# Front.net
KiCad netlist of a schematic drawn in EAGLE
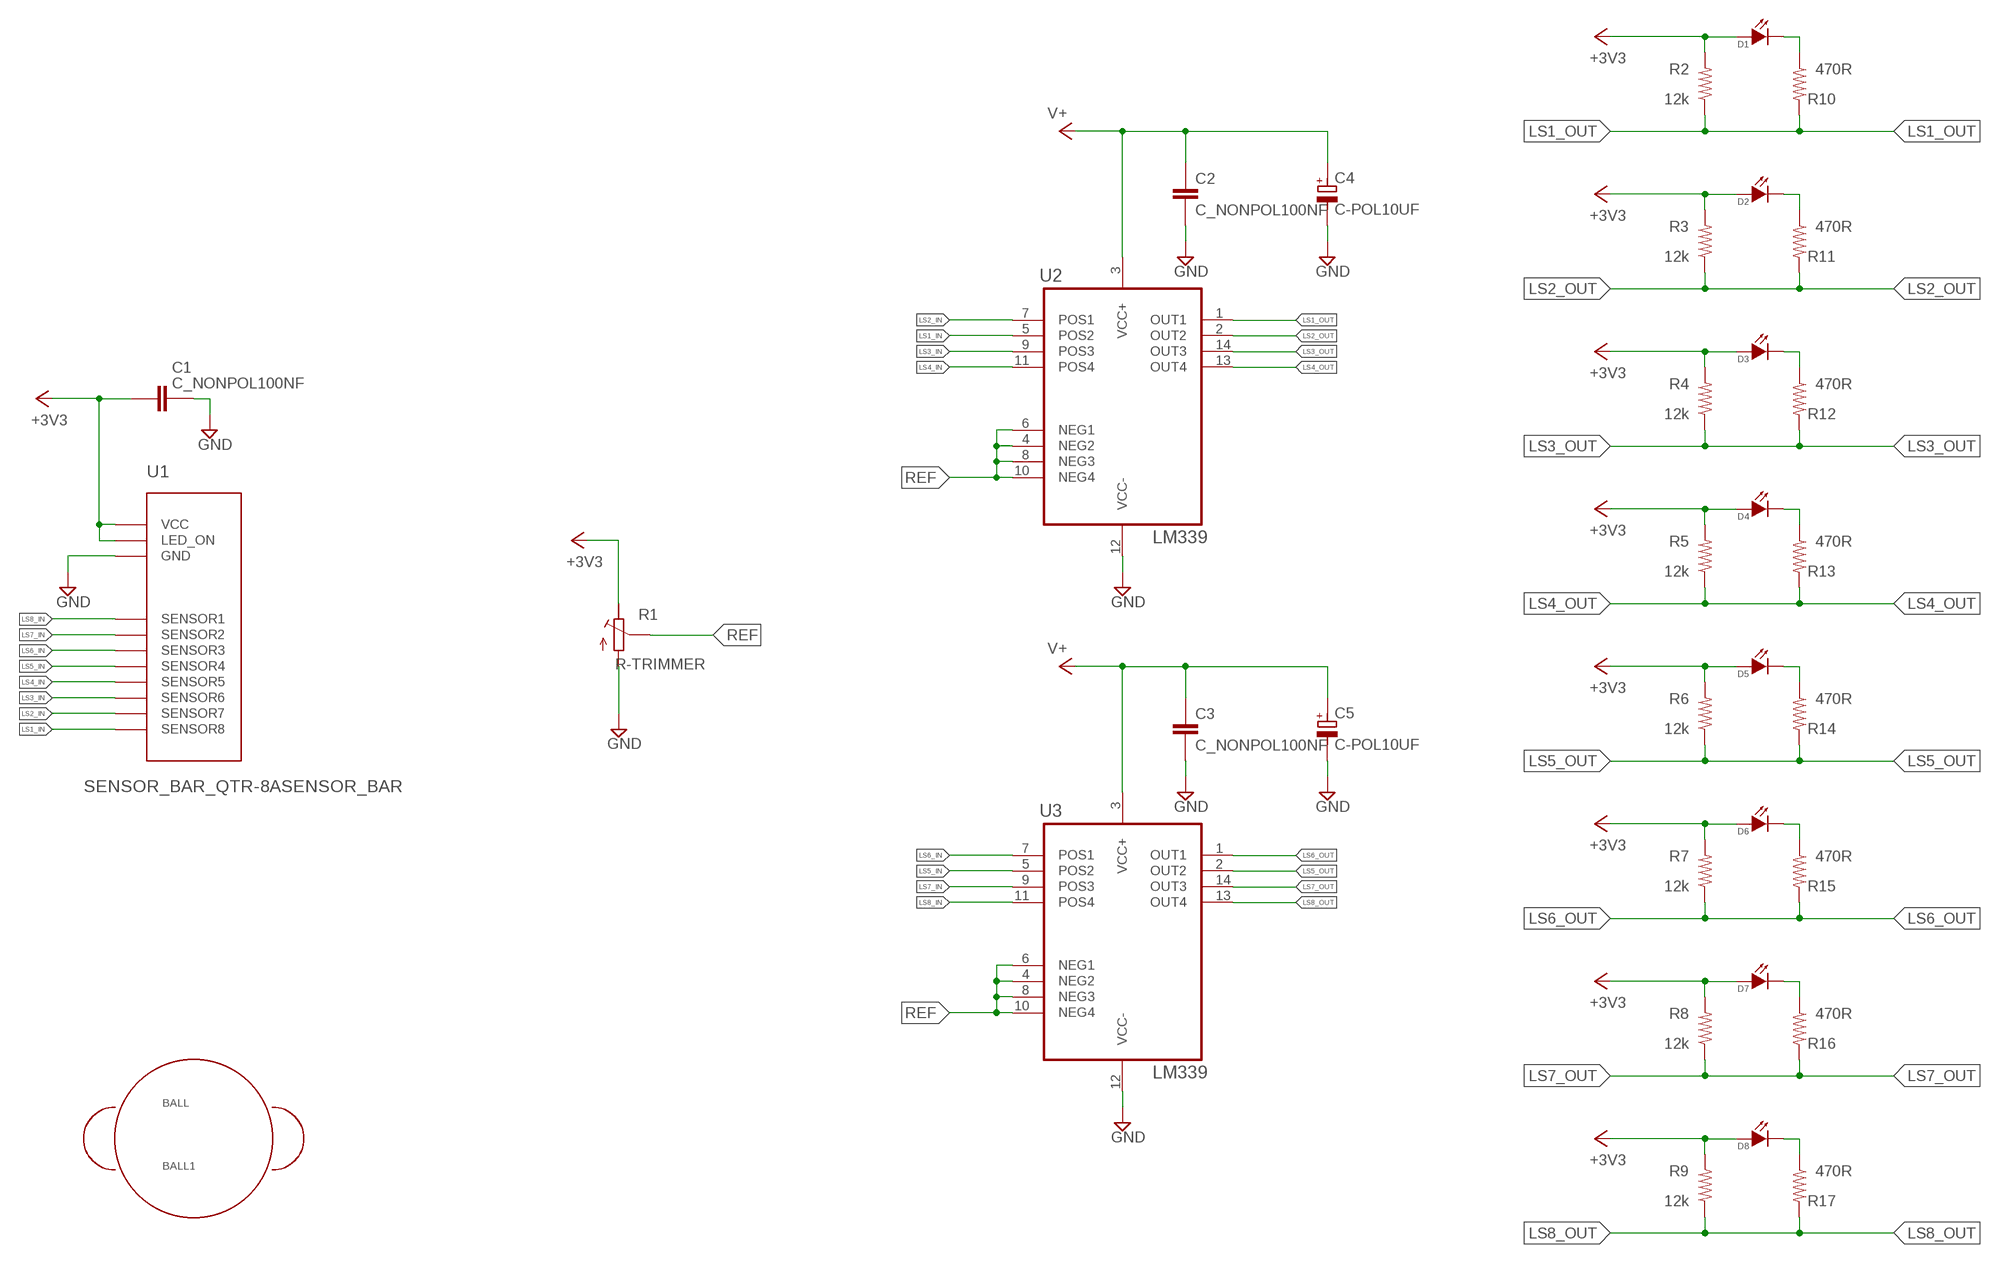
[diagram p0: schematic, sheet 1, part 1 of 2]
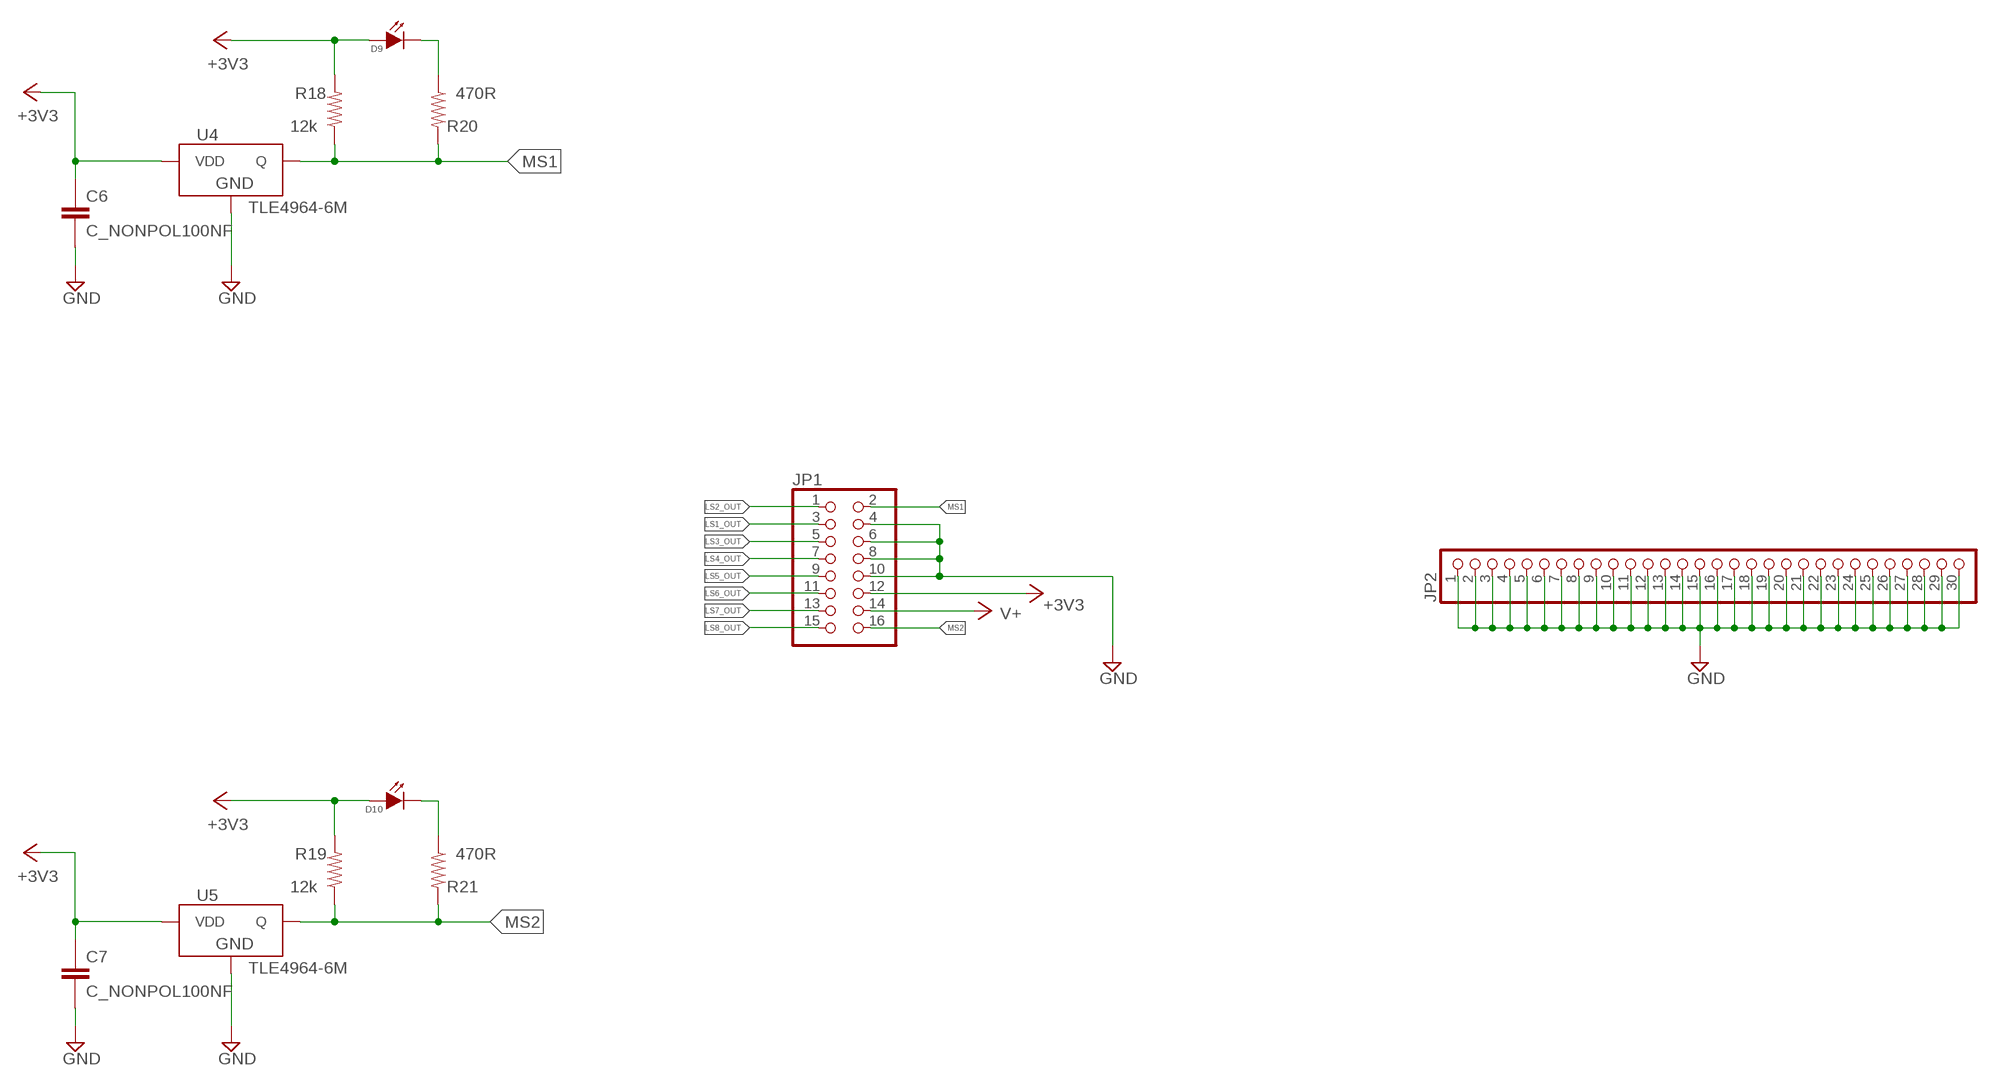
[diagram p1: schematic, sheet 1, part 2 of 2]

(export (version "E")
  (design (tool "Eeschema 10.0.6"))
  (components
    (comp (ref "BALL1")
      (value "BALL")
      (footprint "eagle-import:BALL")
      (libsource (lib "eagle-import") (part "BALL"))
    )
    (comp (ref "C1")
      (value "C_NONPOL100NF")
      (footprint "eagle-import:C1206")
      (libsource (lib "eagle-import") (part "C_NONPOL100NF"))
    )
    (comp (ref "C2")
      (value "C_NONPOL100NF")
      (footprint "eagle-import:C1206")
      (libsource (lib "eagle-import") (part "Line_Follower_LIBV3.1_C_NONPOL100NF"))
    )
    (comp (ref "C3")
      (value "C_NONPOL100NF")
      (footprint "eagle-import:C1206")
      (libsource (lib "eagle-import") (part "Line_Follower_LIBV3.1_C_NONPOL100NF"))
    )
    (comp (ref "C4")
      (value "C-POL10UF")
      (footprint "eagle-import:PANASONIC_B")
      (libsource (lib "eagle-import") (part "C-POL10UF"))
    )
    (comp (ref "C5")
      (value "C-POL10UF")
      (footprint "eagle-import:PANASONIC_B")
      (libsource (lib "eagle-import") (part "C-POL10UF"))
    )
    (comp (ref "C6")
      (value "C_NONPOL100NF")
      (footprint "eagle-import:C1206")
      (libsource (lib "eagle-import") (part "C_NONPOL100NF"))
    )
    (comp (ref "C7")
      (value "C_NONPOL100NF")
      (footprint "eagle-import:C1206")
      (libsource (lib "eagle-import") (part "C_NONPOL100NF"))
    )
    (comp (ref "D1")
      (value "LED")
      (footprint "eagle-import:CHIPLED_1206")
      (libsource (lib "eagle-import") (part "LED"))
    )
    (comp (ref "D2")
      (value "LED")
      (footprint "eagle-import:CHIPLED_1206")
      (libsource (lib "eagle-import") (part "LED"))
    )
    (comp (ref "D3")
      (value "LED")
      (footprint "eagle-import:CHIPLED_1206")
      (libsource (lib "eagle-import") (part "LED"))
    )
    (comp (ref "D4")
      (value "LED")
      (footprint "eagle-import:CHIPLED_1206")
      (libsource (lib "eagle-import") (part "LED"))
    )
    (comp (ref "D5")
      (value "LED")
      (footprint "eagle-import:CHIPLED_1206")
      (libsource (lib "eagle-import") (part "LED"))
    )
    (comp (ref "D6")
      (value "LED")
      (footprint "eagle-import:CHIPLED_1206")
      (libsource (lib "eagle-import") (part "LED"))
    )
    (comp (ref "D7")
      (value "LED")
      (footprint "eagle-import:CHIPLED_1206")
      (libsource (lib "eagle-import") (part "LED"))
    )
    (comp (ref "D8")
      (value "LED")
      (footprint "eagle-import:CHIPLED_1206")
      (libsource (lib "eagle-import") (part "LED"))
    )
    (comp (ref "D9")
      (value "LED")
      (footprint "eagle-import:CHIPLED_1206")
      (libsource (lib "eagle-import") (part "LED"))
    )
    (comp (ref "D10")
      (value "LED")
      (footprint "eagle-import:CHIPLED_1206")
      (libsource (lib "eagle-import") (part "LED"))
    )
    (comp (ref "JP1")
      (value "PINHD-2X8")
      (footprint "eagle-import:2X08")
      (libsource (lib "eagle-import") (part "PINHD-2X8"))
    )
    (comp (ref "JP2")
      (value "PINHD-1X30")
      (footprint "eagle-import:1X30")
      (libsource (lib "eagle-import") (part "PINHD-1X30"))
    )
    (comp (ref "R1")
      (value "R-TRIMMER")
      (footprint "eagle-import:TRIMMER")
      (libsource (lib "eagle-import") (part "R-TRIMMER"))
    )
    (comp (ref "R2")
      (value "12k")
      (footprint "eagle-import:R1206")
      (libsource (lib "eagle-import") (part "R1206"))
    )
    (comp (ref "R3")
      (value "12k")
      (footprint "eagle-import:R1206")
      (libsource (lib "eagle-import") (part "R1206"))
    )
    (comp (ref "R4")
      (value "12k")
      (footprint "eagle-import:R1206")
      (libsource (lib "eagle-import") (part "R1206"))
    )
    (comp (ref "R5")
      (value "12k")
      (footprint "eagle-import:R1206")
      (libsource (lib "eagle-import") (part "R1206"))
    )
    (comp (ref "R6")
      (value "12k")
      (footprint "eagle-import:R1206")
      (libsource (lib "eagle-import") (part "R1206"))
    )
    (comp (ref "R7")
      (value "12k")
      (footprint "eagle-import:R1206")
      (libsource (lib "eagle-import") (part "R1206"))
    )
    (comp (ref "R8")
      (value "12k")
      (footprint "eagle-import:R1206")
      (libsource (lib "eagle-import") (part "R1206"))
    )
    (comp (ref "R9")
      (value "12k")
      (footprint "eagle-import:R1206")
      (libsource (lib "eagle-import") (part "R1206"))
    )
    (comp (ref "R10")
      (value "470R")
      (footprint "eagle-import:R1206")
      (libsource (lib "eagle-import") (part "R1206"))
    )
    (comp (ref "R11")
      (value "470R")
      (footprint "eagle-import:R1206")
      (libsource (lib "eagle-import") (part "R1206"))
    )
    (comp (ref "R12")
      (value "470R")
      (footprint "eagle-import:R1206")
      (libsource (lib "eagle-import") (part "R1206"))
    )
    (comp (ref "R13")
      (value "470R")
      (footprint "eagle-import:R1206")
      (libsource (lib "eagle-import") (part "R1206"))
    )
    (comp (ref "R14")
      (value "470R")
      (footprint "eagle-import:R1206")
      (libsource (lib "eagle-import") (part "R1206"))
    )
    (comp (ref "R15")
      (value "470R")
      (footprint "eagle-import:R1206")
      (libsource (lib "eagle-import") (part "R1206"))
    )
    (comp (ref "R16")
      (value "470R")
      (footprint "eagle-import:R1206")
      (libsource (lib "eagle-import") (part "R1206"))
    )
    (comp (ref "R17")
      (value "470R")
      (footprint "eagle-import:R1206")
      (libsource (lib "eagle-import") (part "R1206"))
    )
    (comp (ref "R18")
      (value "12k")
      (footprint "eagle-import:R1206")
      (libsource (lib "eagle-import") (part "R1206"))
    )
    (comp (ref "R19")
      (value "12k")
      (footprint "eagle-import:R1206")
      (libsource (lib "eagle-import") (part "R1206"))
    )
    (comp (ref "R20")
      (value "470R")
      (footprint "eagle-import:R1206")
      (libsource (lib "eagle-import") (part "R1206"))
    )
    (comp (ref "R21")
      (value "470R")
      (footprint "eagle-import:R1206")
      (libsource (lib "eagle-import") (part "R1206"))
    )
    (comp (ref "U1")
      (value "SENSOR_BAR_QTR-8ASENSOR_BAR")
      (footprint "eagle-import:QTR-8A")
      (libsource (lib "eagle-import") (part "SENSOR_BAR_QTR-8ASENSOR_BAR"))
    )
    (comp (ref "U2")
      (value "LM339")
      (footprint "eagle-import:SO14")
      (libsource (lib "eagle-import") (part "LM339"))
    )
    (comp (ref "U3")
      (value "LM339")
      (footprint "eagle-import:SO14")
      (libsource (lib "eagle-import") (part "LM339"))
    )
    (comp (ref "U4")
      (value "TLE4964-6M")
      (footprint "eagle-import:SOT23-3")
      (libsource (lib "eagle-import") (part "TLE4964-6M"))
    )
    (comp (ref "U5")
      (value "TLE4964-6M")
      (footprint "eagle-import:SOT23-3")
      (libsource (lib "eagle-import") (part "TLE4964-6M"))
    )
  )
  (nets
    (net (code "1") (name "+3V3") (class "Default")
      (node (ref "C1") (pin "2") (pinfunction "2_2") (pintype "passive"))
      (node (ref "C6") (pin "1") (pinfunction "1_1") (pintype "passive"))
      (node (ref "C7") (pin "1") (pinfunction "1_1") (pintype "passive"))
      (node (ref "D1") (pin "A") (pinfunction "A_A") (pintype "bidirectional"))
      (node (ref "D10") (pin "A") (pinfunction "A_A") (pintype "bidirectional"))
      (node (ref "D2") (pin "A") (pinfunction "A_A") (pintype "bidirectional"))
      (node (ref "D3") (pin "A") (pinfunction "A_A") (pintype "bidirectional"))
      (node (ref "D4") (pin "A") (pinfunction "A_A") (pintype "bidirectional"))
      (node (ref "D5") (pin "A") (pinfunction "A_A") (pintype "bidirectional"))
      (node (ref "D6") (pin "A") (pinfunction "A_A") (pintype "bidirectional"))
      (node (ref "D7") (pin "A") (pinfunction "A_A") (pintype "bidirectional"))
      (node (ref "D8") (pin "A") (pinfunction "A_A") (pintype "bidirectional"))
      (node (ref "D9") (pin "A") (pinfunction "A_A") (pintype "bidirectional"))
      (node (ref "JP1") (pin "12") (pinfunction "12_12") (pintype "passive"))
      (node (ref "R1") (pin "2") (pinfunction "E_2") (pintype "passive"))
      (node (ref "R18") (pin "2") (pinfunction "P$2_2") (pintype "passive"))
      (node (ref "R19") (pin "2") (pinfunction "P$2_2") (pintype "passive"))
      (node (ref "R2") (pin "2") (pinfunction "P$2_2") (pintype "passive"))
      (node (ref "R3") (pin "2") (pinfunction "P$2_2") (pintype "passive"))
      (node (ref "R4") (pin "2") (pinfunction "P$2_2") (pintype "passive"))
      (node (ref "R5") (pin "2") (pinfunction "P$2_2") (pintype "passive"))
      (node (ref "R6") (pin "2") (pinfunction "P$2_2") (pintype "passive"))
      (node (ref "R7") (pin "2") (pinfunction "P$2_2") (pintype "passive"))
      (node (ref "R8") (pin "2") (pinfunction "P$2_2") (pintype "passive"))
      (node (ref "R9") (pin "2") (pinfunction "P$2_2") (pintype "passive"))
      (node (ref "U1") (pin "P$2") (pinfunction "LED_ON_P$2") (pintype "input"))
      (node (ref "U1") (pin "P$4") (pinfunction "VCC_P$4") (pintype "power_in"))
      (node (ref "U4") (pin "1") (pinfunction "VDD_1") (pintype "bidirectional"))
      (node (ref "U5") (pin "1") (pinfunction "VDD_1") (pintype "bidirectional"))
    )
    (net (code "2") (name "GND") (class "Default")
      (node (ref "C1") (pin "1") (pinfunction "1_1") (pintype "passive"))
      (node (ref "C2") (pin "2") (pinfunction "2_2") (pintype "passive"))
      (node (ref "C3") (pin "2") (pinfunction "2_2") (pintype "passive"))
      (node (ref "C4") (pin "-") (pinfunction "-_-") (pintype "passive"))
      (node (ref "C5") (pin "-") (pinfunction "-_-") (pintype "passive"))
      (node (ref "C6") (pin "2") (pinfunction "2_2") (pintype "passive"))
      (node (ref "C7") (pin "2") (pinfunction "2_2") (pintype "passive"))
      (node (ref "JP1") (pin "10") (pinfunction "10_10") (pintype "passive"))
      (node (ref "JP1") (pin "4") (pinfunction "4_4") (pintype "passive"))
      (node (ref "JP1") (pin "6") (pinfunction "6_6") (pintype "passive"))
      (node (ref "JP1") (pin "8") (pinfunction "8_8") (pintype "passive"))
      (node (ref "JP2") (pin "1") (pinfunction "1_1") (pintype "passive"))
      (node (ref "JP2") (pin "10") (pinfunction "10_10") (pintype "passive"))
      (node (ref "JP2") (pin "11") (pinfunction "11_11") (pintype "passive"))
      (node (ref "JP2") (pin "12") (pinfunction "12_12") (pintype "passive"))
      (node (ref "JP2") (pin "13") (pinfunction "13_13") (pintype "passive"))
      (node (ref "JP2") (pin "14") (pinfunction "14_14") (pintype "passive"))
      (node (ref "JP2") (pin "15") (pinfunction "15_15") (pintype "passive"))
      (node (ref "JP2") (pin "16") (pinfunction "16_16") (pintype "passive"))
      (node (ref "JP2") (pin "17") (pinfunction "17_17") (pintype "passive"))
      (node (ref "JP2") (pin "18") (pinfunction "18_18") (pintype "passive"))
      (node (ref "JP2") (pin "19") (pinfunction "19_19") (pintype "passive"))
      (node (ref "JP2") (pin "2") (pinfunction "2_2") (pintype "passive"))
      (node (ref "JP2") (pin "20") (pinfunction "20_20") (pintype "passive"))
      (node (ref "JP2") (pin "21") (pinfunction "21_21") (pintype "passive"))
      (node (ref "JP2") (pin "22") (pinfunction "22_22") (pintype "passive"))
      (node (ref "JP2") (pin "23") (pinfunction "23_23") (pintype "passive"))
      (node (ref "JP2") (pin "24") (pinfunction "24_24") (pintype "passive"))
      (node (ref "JP2") (pin "25") (pinfunction "25_25") (pintype "passive"))
      (node (ref "JP2") (pin "26") (pinfunction "26_26") (pintype "passive"))
      (node (ref "JP2") (pin "27") (pinfunction "27_27") (pintype "passive"))
      (node (ref "JP2") (pin "28") (pinfunction "28_28") (pintype "passive"))
      (node (ref "JP2") (pin "29") (pinfunction "29_29") (pintype "passive"))
      (node (ref "JP2") (pin "3") (pinfunction "3_3") (pintype "passive"))
      (node (ref "JP2") (pin "30") (pinfunction "30_30") (pintype "passive"))
      (node (ref "JP2") (pin "4") (pinfunction "4_4") (pintype "passive"))
      (node (ref "JP2") (pin "5") (pinfunction "5_5") (pintype "passive"))
      (node (ref "JP2") (pin "6") (pinfunction "6_6") (pintype "passive"))
      (node (ref "JP2") (pin "7") (pinfunction "7_7") (pintype "passive"))
      (node (ref "JP2") (pin "8") (pinfunction "8_8") (pintype "passive"))
      (node (ref "JP2") (pin "9") (pinfunction "9_9") (pintype "passive"))
      (node (ref "R1") (pin "1") (pinfunction "A_1") (pintype "passive"))
      (node (ref "U1") (pin "P$10") (pinfunction "GND_P$10") (pintype "power_in"))
      (node (ref "U1") (pin "P$12") (pinfunction "GND_P$12") (pintype "power_in"))
      (node (ref "U1") (pin "P$14") (pinfunction "GND_P$14") (pintype "power_in"))
      (node (ref "U1") (pin "P$16") (pinfunction "GND_P$16") (pintype "power_in"))
      (node (ref "U1") (pin "P$6") (pinfunction "GND_P$6") (pintype "power_in"))
      (node (ref "U1") (pin "P$8") (pinfunction "GND_P$8") (pintype "power_in"))
      (node (ref "U2") (pin "12") (pinfunction "VCC-_12") (pintype "power_in"))
      (node (ref "U3") (pin "12") (pinfunction "VCC-_12") (pintype "power_in"))
      (node (ref "U4") (pin "3") (pinfunction "GND_3") (pintype "bidirectional"))
      (node (ref "U5") (pin "3") (pinfunction "GND_3") (pintype "bidirectional"))
    )
    (net (code "3") (name "LS1_IN") (class "Default")
      (node (ref "U1") (pin "P$15") (pinfunction "SENSOR8_P$15") (pintype "output"))
      (node (ref "U2") (pin "5") (pinfunction "POS2_5") (pintype "input"))
    )
    (net (code "4") (name "LS1_OUT") (class "Default")
      (node (ref "JP1") (pin "3") (pinfunction "3_3") (pintype "passive"))
      (node (ref "R10") (pin "2") (pinfunction "P$2_2") (pintype "passive"))
      (node (ref "R2") (pin "1") (pinfunction "P$1_1") (pintype "passive"))
      (node (ref "U2") (pin "1") (pinfunction "OUT1_1") (pintype "output"))
    )
    (net (code "5") (name "LS2_IN") (class "Default")
      (node (ref "U1") (pin "P$13") (pinfunction "SENSOR7_P$13") (pintype "output"))
      (node (ref "U2") (pin "7") (pinfunction "POS1_7") (pintype "input"))
    )
    (net (code "6") (name "LS2_OUT") (class "Default")
      (node (ref "JP1") (pin "1") (pinfunction "1_1") (pintype "passive"))
      (node (ref "R11") (pin "2") (pinfunction "P$2_2") (pintype "passive"))
      (node (ref "R3") (pin "1") (pinfunction "P$1_1") (pintype "passive"))
      (node (ref "U2") (pin "2") (pinfunction "OUT2_2") (pintype "output"))
    )
    (net (code "7") (name "LS3_IN") (class "Default")
      (node (ref "U1") (pin "P$11") (pinfunction "SENSOR6_P$11") (pintype "output"))
      (node (ref "U2") (pin "9") (pinfunction "POS3_9") (pintype "input"))
    )
    (net (code "8") (name "LS3_OUT") (class "Default")
      (node (ref "JP1") (pin "5") (pinfunction "5_5") (pintype "passive"))
      (node (ref "R12") (pin "2") (pinfunction "P$2_2") (pintype "passive"))
      (node (ref "R4") (pin "1") (pinfunction "P$1_1") (pintype "passive"))
      (node (ref "U2") (pin "14") (pinfunction "OUT3_14") (pintype "output"))
    )
    (net (code "9") (name "LS4_IN") (class "Default")
      (node (ref "U1") (pin "P$9") (pinfunction "SENSOR5_P$9") (pintype "output"))
      (node (ref "U2") (pin "11") (pinfunction "POS4_11") (pintype "input"))
    )
    (net (code "10") (name "LS4_OUT") (class "Default")
      (node (ref "JP1") (pin "7") (pinfunction "7_7") (pintype "passive"))
      (node (ref "R13") (pin "2") (pinfunction "P$2_2") (pintype "passive"))
      (node (ref "R5") (pin "1") (pinfunction "P$1_1") (pintype "passive"))
      (node (ref "U2") (pin "13") (pinfunction "OUT4_13") (pintype "output"))
    )
    (net (code "11") (name "LS5_IN") (class "Default")
      (node (ref "U1") (pin "P$7") (pinfunction "SENSOR4_P$7") (pintype "output"))
      (node (ref "U3") (pin "5") (pinfunction "POS2_5") (pintype "input"))
    )
    (net (code "12") (name "LS5_OUT") (class "Default")
      (node (ref "JP1") (pin "9") (pinfunction "9_9") (pintype "passive"))
      (node (ref "R14") (pin "2") (pinfunction "P$2_2") (pintype "passive"))
      (node (ref "R6") (pin "1") (pinfunction "P$1_1") (pintype "passive"))
      (node (ref "U3") (pin "2") (pinfunction "OUT2_2") (pintype "output"))
    )
    (net (code "13") (name "LS6_IN") (class "Default")
      (node (ref "U1") (pin "P$5") (pinfunction "SENSOR3_P$5") (pintype "output"))
      (node (ref "U3") (pin "7") (pinfunction "POS1_7") (pintype "input"))
    )
    (net (code "14") (name "LS6_OUT") (class "Default")
      (node (ref "JP1") (pin "11") (pinfunction "11_11") (pintype "passive"))
      (node (ref "R15") (pin "2") (pinfunction "P$2_2") (pintype "passive"))
      (node (ref "R7") (pin "1") (pinfunction "P$1_1") (pintype "passive"))
      (node (ref "U3") (pin "1") (pinfunction "OUT1_1") (pintype "output"))
    )
    (net (code "15") (name "LS7_IN") (class "Default")
      (node (ref "U1") (pin "P$3") (pinfunction "SENSOR2_P$3") (pintype "output"))
      (node (ref "U3") (pin "9") (pinfunction "POS3_9") (pintype "input"))
    )
    (net (code "16") (name "LS7_OUT") (class "Default")
      (node (ref "JP1") (pin "13") (pinfunction "13_13") (pintype "passive"))
      (node (ref "R16") (pin "2") (pinfunction "P$2_2") (pintype "passive"))
      (node (ref "R8") (pin "1") (pinfunction "P$1_1") (pintype "passive"))
      (node (ref "U3") (pin "14") (pinfunction "OUT3_14") (pintype "output"))
    )
    (net (code "17") (name "LS8_IN") (class "Default")
      (node (ref "U1") (pin "P$1") (pinfunction "SENSOR1_P$1") (pintype "output"))
      (node (ref "U3") (pin "11") (pinfunction "POS4_11") (pintype "input"))
    )
    (net (code "18") (name "LS8_OUT") (class "Default")
      (node (ref "JP1") (pin "15") (pinfunction "15_15") (pintype "passive"))
      (node (ref "R17") (pin "2") (pinfunction "P$2_2") (pintype "passive"))
      (node (ref "R9") (pin "1") (pinfunction "P$1_1") (pintype "passive"))
      (node (ref "U3") (pin "13") (pinfunction "OUT4_13") (pintype "output"))
    )
    (net (code "19") (name "MS1") (class "Default")
      (node (ref "JP1") (pin "2") (pinfunction "2_2") (pintype "passive"))
      (node (ref "R18") (pin "1") (pinfunction "P$1_1") (pintype "passive"))
      (node (ref "R20") (pin "2") (pinfunction "P$2_2") (pintype "passive"))
      (node (ref "U4") (pin "2") (pinfunction "Q_2") (pintype "bidirectional"))
    )
    (net (code "20") (name "MS2") (class "Default")
      (node (ref "JP1") (pin "16") (pinfunction "16_16") (pintype "passive"))
      (node (ref "R19") (pin "1") (pinfunction "P$1_1") (pintype "passive"))
      (node (ref "R21") (pin "2") (pinfunction "P$2_2") (pintype "passive"))
      (node (ref "U5") (pin "2") (pinfunction "Q_2") (pintype "bidirectional"))
    )
    (net (code "21") (name "Net-(D1-K)") (class "Default")
      (node (ref "D1") (pin "C") (pinfunction "K_C") (pintype "bidirectional"))
      (node (ref "R10") (pin "1") (pinfunction "P$1_1") (pintype "passive"))
    )
    (net (code "22") (name "Net-(D2-K)") (class "Default")
      (node (ref "D2") (pin "C") (pinfunction "K_C") (pintype "bidirectional"))
      (node (ref "R11") (pin "1") (pinfunction "P$1_1") (pintype "passive"))
    )
    (net (code "23") (name "Net-(D3-K)") (class "Default")
      (node (ref "D3") (pin "C") (pinfunction "K_C") (pintype "bidirectional"))
      (node (ref "R12") (pin "1") (pinfunction "P$1_1") (pintype "passive"))
    )
    (net (code "24") (name "Net-(D4-K)") (class "Default")
      (node (ref "D4") (pin "C") (pinfunction "K_C") (pintype "bidirectional"))
      (node (ref "R13") (pin "1") (pinfunction "P$1_1") (pintype "passive"))
    )
    (net (code "25") (name "Net-(D5-K)") (class "Default")
      (node (ref "D5") (pin "C") (pinfunction "K_C") (pintype "bidirectional"))
      (node (ref "R14") (pin "1") (pinfunction "P$1_1") (pintype "passive"))
    )
    (net (code "26") (name "Net-(D6-K)") (class "Default")
      (node (ref "D6") (pin "C") (pinfunction "K_C") (pintype "bidirectional"))
      (node (ref "R15") (pin "1") (pinfunction "P$1_1") (pintype "passive"))
    )
    (net (code "27") (name "Net-(D7-K)") (class "Default")
      (node (ref "D7") (pin "C") (pinfunction "K_C") (pintype "bidirectional"))
      (node (ref "R16") (pin "1") (pinfunction "P$1_1") (pintype "passive"))
    )
    (net (code "28") (name "Net-(D8-K)") (class "Default")
      (node (ref "D8") (pin "C") (pinfunction "K_C") (pintype "bidirectional"))
      (node (ref "R17") (pin "1") (pinfunction "P$1_1") (pintype "passive"))
    )
    (net (code "29") (name "Net-(D9-K)") (class "Default")
      (node (ref "D9") (pin "C") (pinfunction "K_C") (pintype "bidirectional"))
      (node (ref "R20") (pin "1") (pinfunction "P$1_1") (pintype "passive"))
    )
    (net (code "30") (name "Net-(D10-K)") (class "Default")
      (node (ref "D10") (pin "C") (pinfunction "K_C") (pintype "bidirectional"))
      (node (ref "R21") (pin "1") (pinfunction "P$1_1") (pintype "passive"))
    )
    (net (code "31") (name "REF") (class "Default")
      (node (ref "R1") (pin "3") (pinfunction "S_3") (pintype "passive"))
      (node (ref "U2") (pin "10") (pinfunction "NEG4_10") (pintype "input"))
      (node (ref "U2") (pin "4") (pinfunction "NEG2_4") (pintype "input"))
      (node (ref "U2") (pin "6") (pinfunction "NEG1_6") (pintype "input"))
      (node (ref "U2") (pin "8") (pinfunction "NEG3_8") (pintype "input"))
      (node (ref "U3") (pin "10") (pinfunction "NEG4_10") (pintype "input"))
      (node (ref "U3") (pin "4") (pinfunction "NEG2_4") (pintype "input"))
      (node (ref "U3") (pin "6") (pinfunction "NEG1_6") (pintype "input"))
      (node (ref "U3") (pin "8") (pinfunction "NEG3_8") (pintype "input"))
    )
    (net (code "32") (name "V+") (class "Default")
      (node (ref "C2") (pin "1") (pinfunction "1_1") (pintype "passive"))
      (node (ref "C3") (pin "1") (pinfunction "1_1") (pintype "passive"))
      (node (ref "C4") (pin "+") (pinfunction "+_+") (pintype "passive"))
      (node (ref "C5") (pin "+") (pinfunction "+_+") (pintype "passive"))
      (node (ref "JP1") (pin "14") (pinfunction "14_14") (pintype "passive"))
      (node (ref "U2") (pin "3") (pinfunction "VCC+_3") (pintype "power_in"))
      (node (ref "U3") (pin "3") (pinfunction "VCC+_3") (pintype "power_in"))
    )
  )
)
